# Schematic.net
KiCad netlist of a schematic drawn in EAGLE
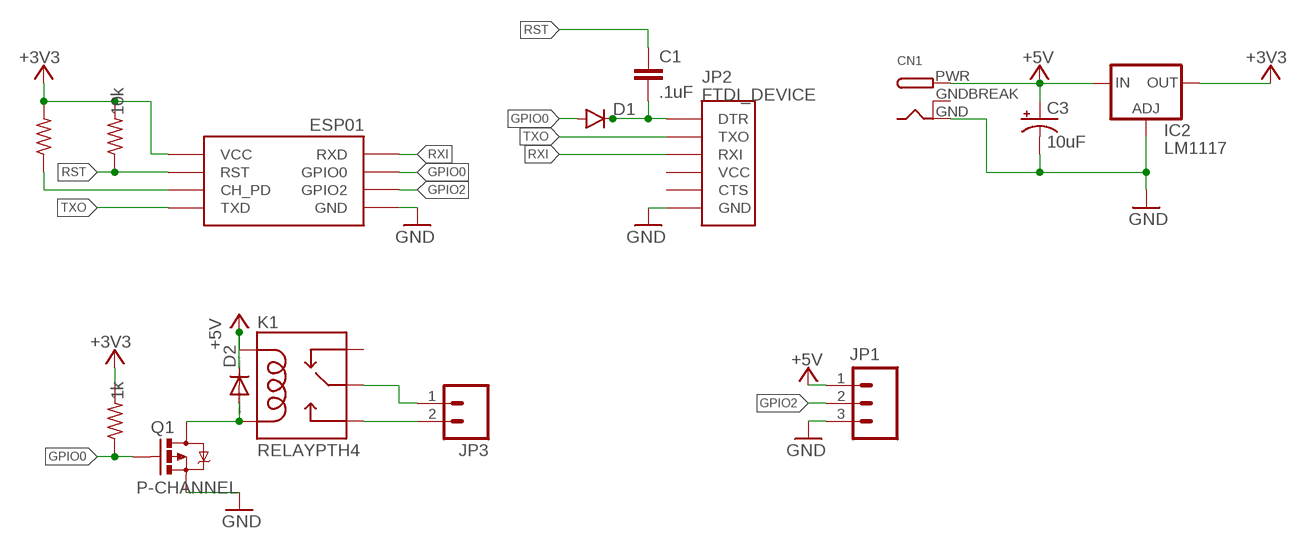
[diagram p0: schematic, sheet 1]

(export (version "E")
  (design (tool "Eeschema 10.0.6"))
  (components
    (comp (ref "C1")
      (value ".1uF")
      (footprint "eagle-import:CAP-PTH-5MM")
      (libsource (lib "eagle-import") (part "CAPPTH1"))
    )
    (comp (ref "C3")
      (value "10uF")
      (footprint "eagle-import:E2-5")
      (libsource (lib "eagle-import") (part "CPOL-USE2-5"))
    )
    (comp (ref "CN1")
      (value "DCBARRELPTH")
      (footprint "eagle-import:DCJACK_2MM_PTH")
      (libsource (lib "eagle-import") (part "DCBARRELPTH"))
    )
    (comp (ref "D1")
      (value "DIODEPTH")
      (footprint "eagle-import:DIODE-1N4001")
      (libsource (lib "eagle-import") (part "DIODEPTH"))
    )
    (comp (ref "D2")
      (value "DIODE-DO41-7.6")
      (footprint "eagle-import:DO41-7.6")
      (libsource (lib "eagle-import") (part "DIODE-DO41-7.6"))
    )
    (comp (ref "ESP-02")
      (value "ESP01")
      (footprint "eagle-import:ESP01")
      (libsource (lib "eagle-import") (part "ESP01"))
    )
    (comp (ref "IC2")
      (value "LM1117")
      (footprint "eagle-import:TO220L1")
      (libsource (lib "eagle-import") (part "LD117A?V"))
    )
    (comp (ref "JP1")
      (value "M03PTH")
      (footprint "eagle-import:1X03")
      (libsource (lib "eagle-import") (part "M03PTH"))
    )
    (comp (ref "JP2")
      (value "FTDI_DEVICE")
      (footprint "eagle-import:FTDI_DEVICE_SIDE")
      (libsource (lib "eagle-import") (part "FTDI_DEVICE"))
    )
    (comp (ref "JP3")
      (value "M025MM")
      (footprint "eagle-import:SCREWTERMINAL-5MM-2")
      (libsource (lib "eagle-import") (part "M025MM"))
    )
    (comp (ref "K1")
      (value "RELAYPTH4")
      (footprint "eagle-import:RELAY-JZC")
      (libsource (lib "eagle-import") (part "RELAYPTH4"))
    )
    (comp (ref "Q1")
      (value "P-CHANNEL")
      (footprint "eagle-import:TO220V")
      (libsource (lib "eagle-import") (part "MOSFET-PCHANNELFQP27P06"))
    )
    (comp (ref "R1")
      (value "10k")
      (footprint "eagle-import:0204V")
      (libsource (lib "eagle-import") (part "R-US_0204/2V"))
    )
    (comp (ref "R2")
      (value "10k")
      (footprint "eagle-import:0204_5")
      (libsource (lib "eagle-import") (part "R-US_0204/5"))
    )
    (comp (ref "R3")
      (value "1k")
      (footprint "eagle-import:0204V")
      (libsource (lib "eagle-import") (part "R-US_0204/2V"))
    )
  )
  (nets
    (net (code "1") (name "+3V3") (class "Default")
      (node (ref "ESP-02") (pin "VCC") (pinfunction "VCC_VCC") (pintype "bidirectional"))
      (node (ref "IC2") (pin "2") (pinfunction "OUT_2") (pintype "passive"))
      (node (ref "R1") (pin "2") (pinfunction "2_2") (pintype "passive"))
      (node (ref "R2") (pin "2") (pinfunction "2_2") (pintype "passive"))
      (node (ref "R3") (pin "2") (pinfunction "2_2") (pintype "passive"))
    )
    (net (code "2") (name "+5V") (class "Default")
      (node (ref "C3") (pin "+") (pinfunction "+_+") (pintype "passive"))
      (node (ref "CN1") (pin "PWR") (pinfunction "PWR_PWR") (pintype "power_in"))
      (node (ref "D2") (pin "C") (pinfunction "C_C") (pintype "passive"))
      (node (ref "IC2") (pin "3") (pinfunction "IN_3") (pintype "input"))
      (node (ref "JP1") (pin "1") (pinfunction "1_1") (pintype "passive"))
      (node (ref "K1") (pin "5") (pinfunction "COIL1_5") (pintype "bidirectional"))
    )
    (net (code "3") (name "/GNDBREAK") (class "Default")
      (node (ref "CN1") (pin "GNDBREAK") (pinfunction "GNDBREAK_GNDBREAK") (pintype "power_in"))
    )
    (net (code "4") (name "GND") (class "Default")
      (node (ref "C3") (pin "-") (pinfunction "-_-") (pintype "passive"))
      (node (ref "CN1") (pin "GND") (pinfunction "GND_GND") (pintype "power_in"))
      (node (ref "ESP-02") (pin "GND") (pinfunction "GND_GND") (pintype "bidirectional"))
      (node (ref "IC2") (pin "1") (pinfunction "ADJ_1") (pintype "input"))
      (node (ref "JP1") (pin "3") (pinfunction "3_3") (pintype "passive"))
      (node (ref "JP2") (pin "P$6") (pinfunction "GND_P$6") (pintype "bidirectional"))
      (node (ref "Q1") (pin "3") (pinfunction "S_3") (pintype "passive"))
    )
    (net (code "5") (name "GPIO0") (class "Default")
      (node (ref "D1") (pin "A") (pinfunction "A_A") (pintype "passive"))
      (node (ref "ESP-02") (pin "GPIO0") (pinfunction "GPIO0_GPIO0") (pintype "bidirectional"))
      (node (ref "Q1") (pin "1") (pinfunction "G_1") (pintype "passive"))
      (node (ref "R3") (pin "1") (pinfunction "1_1") (pintype "passive"))
    )
    (net (code "6") (name "GPIO2") (class "Default")
      (node (ref "ESP-02") (pin "GPIO2") (pinfunction "GPIO2_GPIO2") (pintype "bidirectional"))
      (node (ref "JP1") (pin "2") (pinfunction "2_2") (pintype "passive"))
    )
    (net (code "7") (name "Net-(ESP-02-PadCH_PD)") (class "Default")
      (node (ref "ESP-02") (pin "CH_PD") (pinfunction "CH_PD_CH_PD") (pintype "bidirectional"))
      (node (ref "R2") (pin "1") (pinfunction "1_1") (pintype "passive"))
    )
    (net (code "8") (name "Net-(JP2-DTR)") (class "Default")
      (node (ref "C1") (pin "2") (pinfunction "2_2") (pintype "passive"))
      (node (ref "D1") (pin "C") (pinfunction "C_C") (pintype "passive"))
      (node (ref "JP2") (pin "P$1") (pinfunction "DTR_P$1") (pintype "bidirectional"))
    )
    (net (code "9") (name "Net-(K1-COIL2)") (class "Default")
      (node (ref "D2") (pin "A") (pinfunction "A_A") (pintype "passive"))
      (node (ref "K1") (pin "1") (pinfunction "COIL2_1") (pintype "bidirectional"))
      (node (ref "Q1") (pin "2") (pinfunction "D_2") (pintype "passive"))
    )
    (net (code "10") (name "Net-(K1-MAIN)") (class "Default")
      (node (ref "JP3") (pin "1") (pinfunction "1_1") (pintype "passive"))
      (node (ref "K1") (pin "4") (pinfunction "MAIN_4") (pintype "bidirectional"))
    )
    (net (code "11") (name "Net-(K1-NO)") (class "Default")
      (node (ref "JP3") (pin "2") (pinfunction "2_2") (pintype "passive"))
      (node (ref "K1") (pin "3") (pinfunction "NO_3") (pintype "bidirectional"))
    )
    (net (code "12") (name "RST") (class "Default")
      (node (ref "C1") (pin "1") (pinfunction "1_1") (pintype "passive"))
      (node (ref "ESP-02") (pin "RST") (pinfunction "RST_RST") (pintype "bidirectional"))
      (node (ref "R1") (pin "1") (pinfunction "1_1") (pintype "passive"))
    )
    (net (code "13") (name "RXI") (class "Default")
      (node (ref "ESP-02") (pin "RX") (pinfunction "RXD_RX") (pintype "bidirectional"))
      (node (ref "JP2") (pin "P$3") (pinfunction "RXI_P$3") (pintype "bidirectional"))
    )
    (net (code "14") (name "TXO") (class "Default")
      (node (ref "ESP-02") (pin "TX") (pinfunction "TXD_TX") (pintype "bidirectional"))
      (node (ref "JP2") (pin "P$2") (pinfunction "TXO_P$2") (pintype "bidirectional"))
    )
    (net (code "15") (name "unconnected-(JP2-CTS-PadP$5)") (class "Default")
      (node (ref "JP2") (pin "P$5") (pinfunction "CTS_P$5") (pintype "bidirectional"))
    )
    (net (code "16") (name "unconnected-(JP2-VCC-PadP$4)") (class "Default")
      (node (ref "JP2") (pin "P$4") (pinfunction "VCC_P$4") (pintype "bidirectional"))
    )
    (net (code "17") (name "unconnected-(K1-NC-Pad2)") (class "Default")
      (node (ref "K1") (pin "2") (pinfunction "NC_2") (pintype "bidirectional"))
    )
  )
)
